# ver11.net
KiCad netlist of a schematic drawn in EAGLE
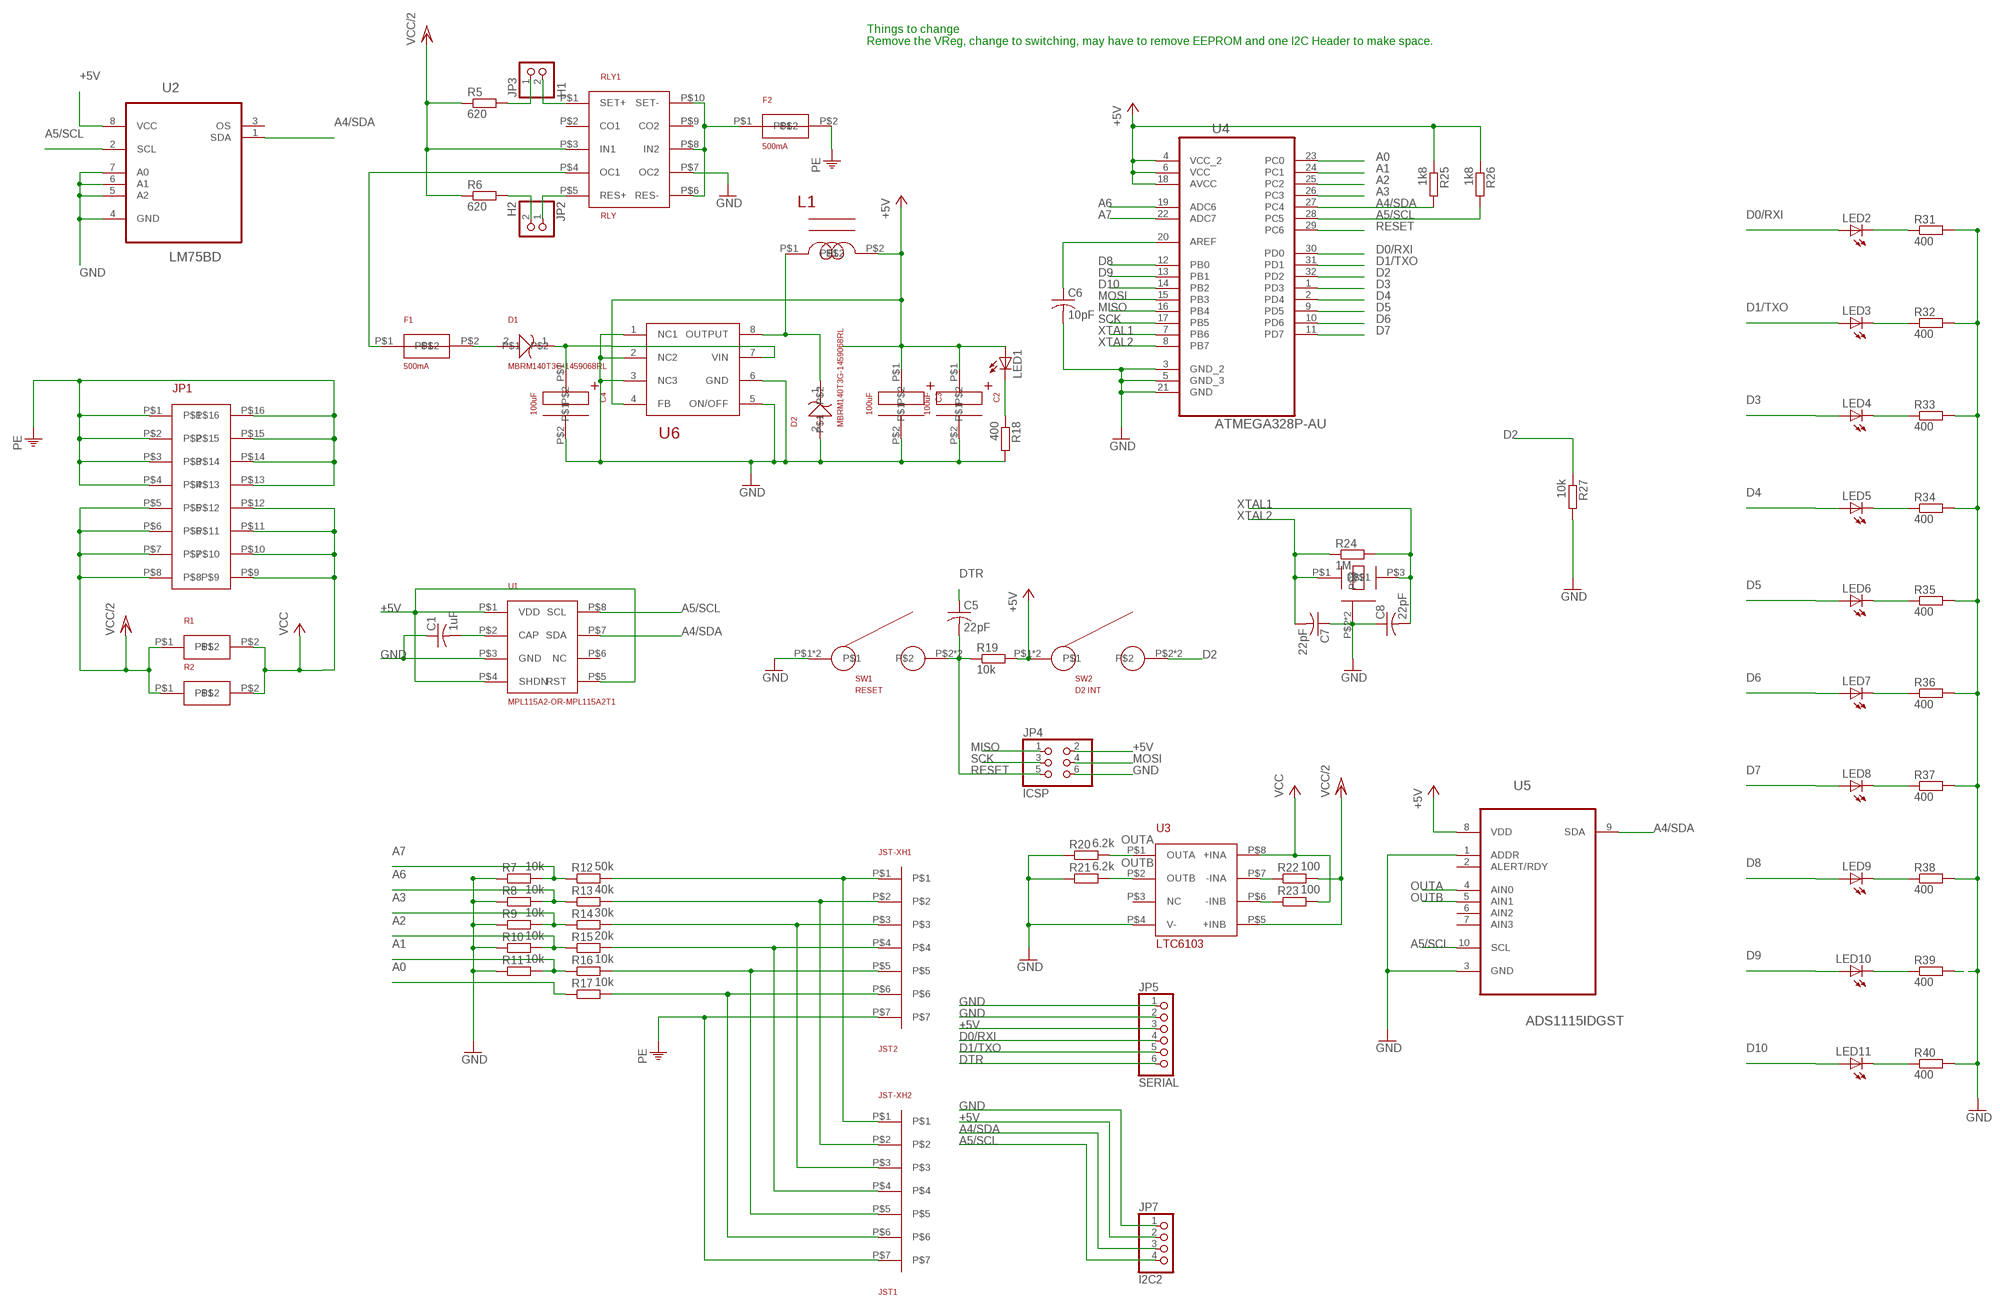
[diagram p0: schematic, sheet 1]

(export (version "E")
  (design (tool "Eeschema 10.0.6"))
  (components
    (comp (ref "C1")
      (value "1uF")
      (footprint "eagle-import:C1206")
      (libsource (lib "eagle-import") (part "C-USC1206"))
    )
    (comp (ref "C2")
      (value "100uF")
      (footprint "eagle-import:EEEFTH101XAP")
      (libsource (lib "eagle-import") (part "EEEFTH101XAP"))
    )
    (comp (ref "C3")
      (value "100uF")
      (footprint "eagle-import:EEEFTH101XAP")
      (libsource (lib "eagle-import") (part "EEEFTH101XAP"))
    )
    (comp (ref "C4")
      (value "100uF")
      (footprint "eagle-import:EEEFTH101XAP")
      (libsource (lib "eagle-import") (part "EEEFTH101XAP"))
    )
    (comp (ref "C5")
      (value "22pF")
      (footprint "eagle-import:C1206")
      (libsource (lib "eagle-import") (part "C-USC1206"))
    )
    (comp (ref "C6")
      (value "10pF")
      (footprint "eagle-import:C1206")
      (libsource (lib "eagle-import") (part "C-USC1206"))
    )
    (comp (ref "C7")
      (value "22pF")
      (footprint "eagle-import:C1206")
      (libsource (lib "eagle-import") (part "C-USC1206"))
    )
    (comp (ref "C8")
      (value "22pF")
      (footprint "eagle-import:C1206")
      (libsource (lib "eagle-import") (part "C-USC1206"))
    )
    (comp (ref "D1")
      (value "MBRM140T3G-1459068RL")
      (footprint "eagle-import:MBRM140T3G-1459068RL")
      (libsource (lib "eagle-import") (part "MBRM140T3G-1459068RL"))
    )
    (comp (ref "D2")
      (value "MBRM140T3G-1459068RL")
      (footprint "eagle-import:MBRM140T3G-1459068RL")
      (libsource (lib "eagle-import") (part "MBRM140T3G-1459068RL"))
    )
    (comp (ref "F1")
      (value "500mA")
      (footprint "eagle-import:MF-MSMF050-2")
      (libsource (lib "eagle-import") (part "MF-MSMF050-2"))
    )
    (comp (ref "F2")
      (value "500mA")
      (footprint "eagle-import:0154.500DR-FUSE-0453.500")
      (libsource (lib "eagle-import") (part "0154.500DR-FUSE-0453.500"))
    )
    (comp (ref "JP1")
      (value "39-29-1167-MOLEX")
      (footprint "eagle-import:39-29-1167-MOLEX")
      (libsource (lib "eagle-import") (part "39-29-1167-MOLEX"))
    )
    (comp (ref "JP2")
      (value "H2")
      (footprint "eagle-import:1X02")
      (libsource (lib "eagle-import") (part "PINHD-1X2"))
    )
    (comp (ref "JP3")
      (value "H1")
      (footprint "eagle-import:1X02")
      (libsource (lib "eagle-import") (part "PINHD-1X2"))
    )
    (comp (ref "JP4")
      (value "ICSP")
      (footprint "eagle-import:2X03")
      (libsource (lib "eagle-import") (part "PINHD-2X3"))
    )
    (comp (ref "JP5")
      (value "SERIAL")
      (footprint "eagle-import:1X06")
      (libsource (lib "eagle-import") (part "PINHD-1X6"))
    )
    (comp (ref "JP7")
      (value "I2C2")
      (footprint "eagle-import:1X04")
      (libsource (lib "eagle-import") (part "PINHD-1X4"))
    )
    (comp (ref "JST-XH1")
      (value "JST2")
      (footprint "eagle-import:JSTXH-7PIN")
      (libsource (lib "eagle-import") (part "JSTXH-7PIN"))
    )
    (comp (ref "JST-XH2")
      (value "JST1")
      (footprint "eagle-import:JSTXH-7PIN")
      (libsource (lib "eagle-import") (part "JSTXH-7PIN"))
    )
    (comp (ref "L1")
      (value "MCSD75-121KU-120UF-INDUCTOR-660MA-1864147")
      (footprint "eagle-import:MCSD75-121KU-120UF-INDUCTOR-660MA-1864147")
      (libsource (lib "eagle-import") (part "MCSD75-121KU-120UF-INDUCTOR-660MA-1864147"))
    )
    (comp (ref "LED1")
      (value "LED1206")
      (footprint "eagle-import:LED-1206")
      (libsource (lib "eagle-import") (part "LED1206"))
    )
    (comp (ref "LED2")
      (value "LED1206")
      (footprint "eagle-import:LED-1206")
      (libsource (lib "eagle-import") (part "LED1206"))
    )
    (comp (ref "LED3")
      (value "LED1206")
      (footprint "eagle-import:LED-1206")
      (libsource (lib "eagle-import") (part "LED1206"))
    )
    (comp (ref "LED4")
      (value "LED1206")
      (footprint "eagle-import:LED-1206")
      (libsource (lib "eagle-import") (part "LED1206"))
    )
    (comp (ref "LED5")
      (value "LED1206")
      (footprint "eagle-import:LED-1206")
      (libsource (lib "eagle-import") (part "LED1206"))
    )
    (comp (ref "LED6")
      (value "LED1206")
      (footprint "eagle-import:LED-1206")
      (libsource (lib "eagle-import") (part "LED1206"))
    )
    (comp (ref "LED7")
      (value "LED1206")
      (footprint "eagle-import:LED-1206")
      (libsource (lib "eagle-import") (part "LED1206"))
    )
    (comp (ref "LED8")
      (value "LED1206")
      (footprint "eagle-import:LED-1206")
      (libsource (lib "eagle-import") (part "LED1206"))
    )
    (comp (ref "LED9")
      (value "LED1206")
      (footprint "eagle-import:LED-1206")
      (libsource (lib "eagle-import") (part "LED1206"))
    )
    (comp (ref "LED10")
      (value "LED1206")
      (footprint "eagle-import:LED-1206")
      (libsource (lib "eagle-import") (part "LED1206"))
    )
    (comp (ref "LED11")
      (value "LED1206")
      (footprint "eagle-import:LED-1206")
      (libsource (lib "eagle-import") (part "LED1206"))
    )
    (comp (ref "R1")
      (value "OARSXPR002FLF")
      (footprint "eagle-import:OARSXPR002FLF")
      (libsource (lib "eagle-import") (part "OARSXPR002FLF"))
    )
    (comp (ref "R2")
      (value "OARSXPR002FLF")
      (footprint "eagle-import:OARSXPR002FLF")
      (libsource (lib "eagle-import") (part "OARSXPR002FLF"))
    )
    (comp (ref "R5")
      (value "620")
      (footprint "eagle-import:R1206")
      (libsource (lib "eagle-import") (part "R-EU_R1206"))
    )
    (comp (ref "R6")
      (value "620")
      (footprint "eagle-import:R1206")
      (libsource (lib "eagle-import") (part "R-EU_R1206"))
    )
    (comp (ref "R7")
      (value "10k")
      (footprint "eagle-import:R1206")
      (libsource (lib "eagle-import") (part "R-EU_R1206"))
    )
    (comp (ref "R8")
      (value "10k")
      (footprint "eagle-import:R1206")
      (libsource (lib "eagle-import") (part "R-EU_R1206"))
    )
    (comp (ref "R9")
      (value "10k")
      (footprint "eagle-import:R1206")
      (libsource (lib "eagle-import") (part "R-EU_R1206"))
    )
    (comp (ref "R10")
      (value "10k")
      (footprint "eagle-import:R1206")
      (libsource (lib "eagle-import") (part "R-EU_R1206"))
    )
    (comp (ref "R11")
      (value "10k")
      (footprint "eagle-import:R1206")
      (libsource (lib "eagle-import") (part "R-EU_R1206"))
    )
    (comp (ref "R12")
      (value "50k")
      (footprint "eagle-import:R1206")
      (libsource (lib "eagle-import") (part "R-EU_R1206"))
    )
    (comp (ref "R13")
      (value "40k")
      (footprint "eagle-import:R1206")
      (libsource (lib "eagle-import") (part "R-EU_R1206"))
    )
    (comp (ref "R14")
      (value "30k")
      (footprint "eagle-import:R1206")
      (libsource (lib "eagle-import") (part "R-EU_R1206"))
    )
    (comp (ref "R15")
      (value "20k")
      (footprint "eagle-import:R1206")
      (libsource (lib "eagle-import") (part "R-EU_R1206"))
    )
    (comp (ref "R16")
      (value "10k")
      (footprint "eagle-import:R1206")
      (libsource (lib "eagle-import") (part "R-EU_R1206"))
    )
    (comp (ref "R17")
      (value "10k")
      (footprint "eagle-import:R1206")
      (libsource (lib "eagle-import") (part "R-EU_R1206"))
    )
    (comp (ref "R18")
      (value "400")
      (footprint "eagle-import:R1206")
      (libsource (lib "eagle-import") (part "R-EU_R1206"))
    )
    (comp (ref "R19")
      (value "10k")
      (footprint "eagle-import:R1206")
      (libsource (lib "eagle-import") (part "R-EU_R1206"))
    )
    (comp (ref "R20")
      (value "6.2k")
      (footprint "eagle-import:R1206")
      (libsource (lib "eagle-import") (part "R-EU_R1206"))
    )
    (comp (ref "R21")
      (value "6.2k")
      (footprint "eagle-import:R1206")
      (libsource (lib "eagle-import") (part "R-EU_R1206"))
    )
    (comp (ref "R22")
      (value "100")
      (footprint "eagle-import:R1206")
      (libsource (lib "eagle-import") (part "R-EU_R1206"))
    )
    (comp (ref "R23")
      (value "100")
      (footprint "eagle-import:R1206")
      (libsource (lib "eagle-import") (part "R-EU_R1206"))
    )
    (comp (ref "R24")
      (value "1M")
      (footprint "eagle-import:R1206")
      (libsource (lib "eagle-import") (part "R-EU_R1206"))
    )
    (comp (ref "R25")
      (value "1k8")
      (footprint "eagle-import:R1206")
      (libsource (lib "eagle-import") (part "R-EU_R1206"))
    )
    (comp (ref "R26")
      (value "1k8")
      (footprint "eagle-import:R1206")
      (libsource (lib "eagle-import") (part "R-EU_R1206"))
    )
    (comp (ref "R27")
      (value "10k")
      (footprint "eagle-import:R1206")
      (libsource (lib "eagle-import") (part "R-EU_R1206"))
    )
    (comp (ref "R31")
      (value "400")
      (footprint "eagle-import:R1206")
      (libsource (lib "eagle-import") (part "R-EU_R1206"))
    )
    (comp (ref "R32")
      (value "400")
      (footprint "eagle-import:R1206")
      (libsource (lib "eagle-import") (part "R-EU_R1206"))
    )
    (comp (ref "R33")
      (value "400")
      (footprint "eagle-import:R1206")
      (libsource (lib "eagle-import") (part "R-EU_R1206"))
    )
    (comp (ref "R34")
      (value "400")
      (footprint "eagle-import:R1206")
      (libsource (lib "eagle-import") (part "R-EU_R1206"))
    )
    (comp (ref "R35")
      (value "400")
      (footprint "eagle-import:R1206")
      (libsource (lib "eagle-import") (part "R-EU_R1206"))
    )
    (comp (ref "R36")
      (value "400")
      (footprint "eagle-import:R1206")
      (libsource (lib "eagle-import") (part "R-EU_R1206"))
    )
    (comp (ref "R37")
      (value "400")
      (footprint "eagle-import:R1206")
      (libsource (lib "eagle-import") (part "R-EU_R1206"))
    )
    (comp (ref "R38")
      (value "400")
      (footprint "eagle-import:R1206")
      (libsource (lib "eagle-import") (part "R-EU_R1206"))
    )
    (comp (ref "R39")
      (value "400")
      (footprint "eagle-import:R1206")
      (libsource (lib "eagle-import") (part "R-EU_R1206"))
    )
    (comp (ref "R40")
      (value "400")
      (footprint "eagle-import:R1206")
      (libsource (lib "eagle-import") (part "R-EU_R1206"))
    )
    (comp (ref "RLY1")
      (value "RLY")
      (footprint "eagle-import:3-1393788-3")
      (libsource (lib "eagle-import") (part "3-1393788-3"))
    )
    (comp (ref "SW1")
      (value "RESET")
      (footprint "eagle-import:MC32829")
      (libsource (lib "eagle-import") (part "MC32829"))
    )
    (comp (ref "SW2")
      (value "D2 INT")
      (footprint "eagle-import:MC32829")
      (libsource (lib "eagle-import") (part "MC32829"))
    )
    (comp (ref "U1")
      (value "MPL115A2-OR-MPL115A2T1")
      (footprint "eagle-import:MPL115A2-OR-MPL115A2T1")
      (libsource (lib "eagle-import") (part "MPL115A2-OR-MPL115A2T1"))
    )
    (comp (ref "U2")
      (value "LM75BD")
      (footprint "eagle-import:SOIC127P600X175-8N")
      (libsource (lib "eagle-import") (part "LM75BD"))
    )
    (comp (ref "U3")
      (value "LTC6103")
      (footprint "eagle-import:LTC6103CMS8#PBF")
      (libsource (lib "eagle-import") (part "LTC6103CMS8#PBF"))
    )
    (comp (ref "U4")
      (value "ATMEGA328P-AU")
      (footprint "eagle-import:QFP80P900X900X120-32N")
      (libsource (lib "eagle-import") (part "ATMEGA328P-AU"))
    )
    (comp (ref "U5")
      (value "ADS1115IDGST")
      (footprint "eagle-import:SOP50P490X110-10N")
      (libsource (lib "eagle-import") (part "ADS1115IDGST"))
    )
    (comp (ref "U6")
      (value "VOLTREG-LM2594MX-5.0/NOPB-1496090")
      (footprint "eagle-import:SO08")
      (libsource (lib "eagle-import") (part "VOLTREG-LM2594MX-5.0/NOPB-1496090"))
    )
    (comp (ref "XT1")
      (value "ABMM2-16.000MHZ-E2-T")
      (footprint "eagle-import:ABMM2-16.000MHZ-E2-T")
      (libsource (lib "eagle-import") (part "ABMM2-16.000MHZ-E2-T"))
    )
  )
  (nets
    (net (code "1") (name "+5V") (class "Default")
      (node (ref "C2") (pin "P$1") (pinfunction "P$1_P$1") (pintype "bidirectional"))
      (node (ref "C3") (pin "P$1") (pinfunction "P$1_P$1") (pintype "bidirectional"))
      (node (ref "JP4") (pin "2") (pinfunction "2_2") (pintype "passive"))
      (node (ref "JP5") (pin "3") (pinfunction "3_3") (pintype "passive"))
      (node (ref "JP7") (pin "2") (pinfunction "2_2") (pintype "passive"))
      (node (ref "L1") (pin "P$2") (pinfunction "P$2_P$2") (pintype "bidirectional"))
      (node (ref "LED1") (pin "A") (pinfunction "A_A") (pintype "passive"))
      (node (ref "R19") (pin "2") (pinfunction "2_2") (pintype "passive"))
      (node (ref "R25") (pin "1") (pinfunction "1_1") (pintype "passive"))
      (node (ref "R26") (pin "1") (pinfunction "1_1") (pintype "passive"))
      (node (ref "SW2") (pin "P$1") (pinfunction "P$1_P$1") (pintype "bidirectional"))
      (node (ref "SW2") (pin "P$4") (pinfunction "P$1_P$4") (pintype "bidirectional"))
      (node (ref "U1") (pin "P$1") (pinfunction "VDD_P$1") (pintype "bidirectional"))
      (node (ref "U1") (pin "P$4") (pinfunction "SHDN_P$4") (pintype "bidirectional"))
      (node (ref "U1") (pin "P$5") (pinfunction "RST_P$5") (pintype "bidirectional"))
      (node (ref "U2") (pin "8") (pinfunction "VCC_8") (pintype "power_in"))
      (node (ref "U4") (pin "18") (pinfunction "AVCC_18") (pintype "power_in"))
      (node (ref "U4") (pin "4") (pinfunction "VCC_2_4") (pintype "power_in"))
      (node (ref "U4") (pin "6") (pinfunction "VCC_6") (pintype "power_in"))
      (node (ref "U5") (pin "8") (pinfunction "VDD_8") (pintype "power_in"))
      (node (ref "U6") (pin "4") (pinfunction "FB_4") (pintype "bidirectional"))
    )
    (net (code "2") (name "/A0") (class "Default")
      (node (ref "R17") (pin "1") (pinfunction "1_1") (pintype "passive"))
      (node (ref "U4") (pin "23") (pinfunction "PC0_23") (pintype "bidirectional"))
    )
    (net (code "3") (name "/A1") (class "Default")
      (node (ref "R11") (pin "2") (pinfunction "2_2") (pintype "passive"))
      (node (ref "R16") (pin "1") (pinfunction "1_1") (pintype "passive"))
      (node (ref "U4") (pin "24") (pinfunction "PC1_24") (pintype "bidirectional"))
    )
    (net (code "4") (name "/A2") (class "Default")
      (node (ref "R10") (pin "2") (pinfunction "2_2") (pintype "passive"))
      (node (ref "R15") (pin "1") (pinfunction "1_1") (pintype "passive"))
      (node (ref "U4") (pin "25") (pinfunction "PC2_25") (pintype "bidirectional"))
    )
    (net (code "5") (name "/A3") (class "Default")
      (node (ref "R14") (pin "1") (pinfunction "1_1") (pintype "passive"))
      (node (ref "R9") (pin "2") (pinfunction "2_2") (pintype "passive"))
      (node (ref "U4") (pin "26") (pinfunction "PC3_26") (pintype "bidirectional"))
    )
    (net (code "6") (name "/A4{slash}SDA") (class "Default")
      (node (ref "JP7") (pin "3") (pinfunction "3_3") (pintype "passive"))
      (node (ref "R25") (pin "2") (pinfunction "2_2") (pintype "passive"))
      (node (ref "U1") (pin "P$7") (pinfunction "SDA_P$7") (pintype "bidirectional"))
      (node (ref "U2") (pin "1") (pinfunction "SDA_1") (pintype "bidirectional"))
      (node (ref "U4") (pin "27") (pinfunction "PC4_27") (pintype "bidirectional"))
      (node (ref "U5") (pin "9") (pinfunction "SDA_9") (pintype "bidirectional"))
    )
    (net (code "7") (name "/A5{slash}SCL") (class "Default")
      (node (ref "JP7") (pin "4") (pinfunction "4_4") (pintype "passive"))
      (node (ref "R26") (pin "2") (pinfunction "2_2") (pintype "passive"))
      (node (ref "U1") (pin "P$8") (pinfunction "SCL_P$8") (pintype "bidirectional"))
      (node (ref "U2") (pin "2") (pinfunction "SCL_2") (pintype "input"))
      (node (ref "U4") (pin "28") (pinfunction "PC5_28") (pintype "bidirectional"))
      (node (ref "U5") (pin "10") (pinfunction "SCL_10") (pintype "input"))
    )
    (net (code "8") (name "/A6") (class "Default")
      (node (ref "R13") (pin "1") (pinfunction "1_1") (pintype "passive"))
      (node (ref "R8") (pin "2") (pinfunction "2_2") (pintype "passive"))
      (node (ref "U4") (pin "19") (pinfunction "ADC6_19") (pintype "input"))
    )
    (net (code "9") (name "/A7") (class "Default")
      (node (ref "R12") (pin "1") (pinfunction "1_1") (pintype "passive"))
      (node (ref "R7") (pin "2") (pinfunction "2_2") (pintype "passive"))
      (node (ref "U4") (pin "22") (pinfunction "ADC7_22") (pintype "input"))
    )
    (net (code "10") (name "/D0{slash}RXI") (class "Default")
      (node (ref "JP5") (pin "4") (pinfunction "4_4") (pintype "passive"))
      (node (ref "LED2") (pin "A") (pinfunction "A_A") (pintype "passive"))
      (node (ref "U4") (pin "30") (pinfunction "PD0_30") (pintype "bidirectional"))
    )
    (net (code "11") (name "/D1{slash}TXO") (class "Default")
      (node (ref "JP5") (pin "5") (pinfunction "5_5") (pintype "passive"))
      (node (ref "LED3") (pin "A") (pinfunction "A_A") (pintype "passive"))
      (node (ref "U4") (pin "31") (pinfunction "PD1_31") (pintype "bidirectional"))
    )
    (net (code "12") (name "/D2") (class "Default")
      (node (ref "R27") (pin "1") (pinfunction "1_1") (pintype "passive"))
      (node (ref "SW2") (pin "P$2") (pinfunction "P$2_P$2") (pintype "bidirectional"))
      (node (ref "SW2") (pin "P$3") (pinfunction "P$2_P$3") (pintype "bidirectional"))
      (node (ref "U4") (pin "32") (pinfunction "PD2_32") (pintype "bidirectional"))
    )
    (net (code "13") (name "/D3") (class "Default")
      (node (ref "LED4") (pin "A") (pinfunction "A_A") (pintype "passive"))
      (node (ref "U4") (pin "1") (pinfunction "PD3_1") (pintype "bidirectional"))
    )
    (net (code "14") (name "/D4") (class "Default")
      (node (ref "LED5") (pin "A") (pinfunction "A_A") (pintype "passive"))
      (node (ref "U4") (pin "2") (pinfunction "PD4_2") (pintype "bidirectional"))
    )
    (net (code "15") (name "/D5") (class "Default")
      (node (ref "LED6") (pin "A") (pinfunction "A_A") (pintype "passive"))
      (node (ref "U4") (pin "9") (pinfunction "PD5_9") (pintype "bidirectional"))
    )
    (net (code "16") (name "/D6") (class "Default")
      (node (ref "LED7") (pin "A") (pinfunction "A_A") (pintype "passive"))
      (node (ref "U4") (pin "10") (pinfunction "PD6_10") (pintype "bidirectional"))
    )
    (net (code "17") (name "/D7") (class "Default")
      (node (ref "LED8") (pin "A") (pinfunction "A_A") (pintype "passive"))
      (node (ref "U4") (pin "11") (pinfunction "PD7_11") (pintype "bidirectional"))
    )
    (net (code "18") (name "/D8") (class "Default")
      (node (ref "LED9") (pin "A") (pinfunction "A_A") (pintype "passive"))
      (node (ref "U4") (pin "12") (pinfunction "PB0_12") (pintype "bidirectional"))
    )
    (net (code "19") (name "/D9") (class "Default")
      (node (ref "LED10") (pin "A") (pinfunction "A_A") (pintype "passive"))
      (node (ref "U4") (pin "13") (pinfunction "PB1_13") (pintype "bidirectional"))
    )
    (net (code "20") (name "/D10") (class "Default")
      (node (ref "LED11") (pin "A") (pinfunction "A_A") (pintype "passive"))
      (node (ref "U4") (pin "14") (pinfunction "PB2_14") (pintype "bidirectional"))
    )
    (net (code "21") (name "/DTR") (class "Default")
      (node (ref "C5") (pin "1") (pinfunction "1_1") (pintype "passive"))
      (node (ref "JP5") (pin "6") (pinfunction "6_6") (pintype "passive"))
    )
    (net (code "22") (name "/MISO") (class "Default")
      (node (ref "JP4") (pin "1") (pinfunction "1_1") (pintype "passive"))
      (node (ref "U4") (pin "16") (pinfunction "PB4_16") (pintype "bidirectional"))
    )
    (net (code "23") (name "/MOSI") (class "Default")
      (node (ref "JP4") (pin "4") (pinfunction "4_4") (pintype "passive"))
      (node (ref "U4") (pin "15") (pinfunction "PB3_15") (pintype "bidirectional"))
    )
    (net (code "24") (name "/OUTA") (class "Default")
      (node (ref "R20") (pin "2") (pinfunction "2_2") (pintype "passive"))
      (node (ref "U3") (pin "P$1") (pinfunction "OUTA_P$1") (pintype "bidirectional"))
      (node (ref "U5") (pin "4") (pinfunction "AIN0_4") (pintype "input"))
    )
    (net (code "25") (name "/OUTB") (class "Default")
      (node (ref "R21") (pin "2") (pinfunction "2_2") (pintype "passive"))
      (node (ref "U3") (pin "P$2") (pinfunction "OUTB_P$2") (pintype "bidirectional"))
      (node (ref "U5") (pin "5") (pinfunction "AIN1_5") (pintype "input"))
    )
    (net (code "26") (name "/RESET") (class "Default")
      (node (ref "C5") (pin "2") (pinfunction "2_2") (pintype "passive"))
      (node (ref "JP4") (pin "5") (pinfunction "5_5") (pintype "passive"))
      (node (ref "R19") (pin "1") (pinfunction "1_1") (pintype "passive"))
      (node (ref "SW1") (pin "P$2") (pinfunction "P$2_P$2") (pintype "bidirectional"))
      (node (ref "SW1") (pin "P$3") (pinfunction "P$2_P$3") (pintype "bidirectional"))
      (node (ref "U4") (pin "29") (pinfunction "PC6_29") (pintype "bidirectional"))
    )
    (net (code "27") (name "/SCK") (class "Default")
      (node (ref "JP4") (pin "3") (pinfunction "3_3") (pintype "passive"))
      (node (ref "U4") (pin "17") (pinfunction "PB5_17") (pintype "bidirectional"))
    )
    (net (code "28") (name "/XTAL1") (class "Default")
      (node (ref "C8") (pin "2") (pinfunction "2_2") (pintype "passive"))
      (node (ref "R24") (pin "2") (pinfunction "2_2") (pintype "passive"))
      (node (ref "U4") (pin "7") (pinfunction "PB6_7") (pintype "bidirectional"))
      (node (ref "XT1") (pin "P$3") (pinfunction "P$2_P$3") (pintype "bidirectional"))
    )
    (net (code "29") (name "/XTAL2") (class "Default")
      (node (ref "C7") (pin "2") (pinfunction "2_2") (pintype "passive"))
      (node (ref "R24") (pin "1") (pinfunction "1_1") (pintype "passive"))
      (node (ref "U4") (pin "8") (pinfunction "PB7_8") (pintype "bidirectional"))
      (node (ref "XT1") (pin "P$1") (pinfunction "P$1_P$1") (pintype "bidirectional"))
    )
    (net (code "30") (name "GND") (class "Default")
      (node (ref "C1") (pin "1") (pinfunction "1_1") (pintype "passive"))
      (node (ref "C2") (pin "P$2") (pinfunction "P$2_P$2") (pintype "bidirectional"))
      (node (ref "C3") (pin "P$2") (pinfunction "P$2_P$2") (pintype "bidirectional"))
      (node (ref "C4") (pin "P$2") (pinfunction "P$2_P$2") (pintype "bidirectional"))
      (node (ref "C6") (pin "2") (pinfunction "2_2") (pintype "passive"))
      (node (ref "C7") (pin "1") (pinfunction "1_1") (pintype "passive"))
      (node (ref "C8") (pin "1") (pinfunction "1_1") (pintype "passive"))
      (node (ref "D2") (pin "2") (pinfunction "P$2_2") (pintype "bidirectional"))
      (node (ref "JP4") (pin "6") (pinfunction "6_6") (pintype "passive"))
      (node (ref "JP5") (pin "1") (pinfunction "1_1") (pintype "passive"))
      (node (ref "JP5") (pin "2") (pinfunction "2_2") (pintype "passive"))
      (node (ref "JP7") (pin "1") (pinfunction "1_1") (pintype "passive"))
      (node (ref "R10") (pin "1") (pinfunction "1_1") (pintype "passive"))
      (node (ref "R11") (pin "1") (pinfunction "1_1") (pintype "passive"))
      (node (ref "R18") (pin "2") (pinfunction "2_2") (pintype "passive"))
      (node (ref "R20") (pin "1") (pinfunction "1_1") (pintype "passive"))
      (node (ref "R21") (pin "1") (pinfunction "1_1") (pintype "passive"))
      (node (ref "R27") (pin "2") (pinfunction "2_2") (pintype "passive"))
      (node (ref "R31") (pin "2") (pinfunction "2_2") (pintype "passive"))
      (node (ref "R32") (pin "2") (pinfunction "2_2") (pintype "passive"))
      (node (ref "R33") (pin "2") (pinfunction "2_2") (pintype "passive"))
      (node (ref "R34") (pin "2") (pinfunction "2_2") (pintype "passive"))
      (node (ref "R35") (pin "2") (pinfunction "2_2") (pintype "passive"))
      (node (ref "R36") (pin "2") (pinfunction "2_2") (pintype "passive"))
      (node (ref "R37") (pin "2") (pinfunction "2_2") (pintype "passive"))
      (node (ref "R38") (pin "2") (pinfunction "2_2") (pintype "passive"))
      (node (ref "R39") (pin "2") (pinfunction "2_2") (pintype "passive"))
      (node (ref "R40") (pin "2") (pinfunction "2_2") (pintype "passive"))
      (node (ref "R7") (pin "1") (pinfunction "1_1") (pintype "passive"))
      (node (ref "R8") (pin "1") (pinfunction "1_1") (pintype "passive"))
      (node (ref "R9") (pin "1") (pinfunction "1_1") (pintype "passive"))
      (node (ref "RLY1") (pin "P$7") (pinfunction "OC2_P$7") (pintype "bidirectional"))
      (node (ref "SW1") (pin "P$1") (pinfunction "P$1_P$1") (pintype "bidirectional"))
      (node (ref "SW1") (pin "P$4") (pinfunction "P$1_P$4") (pintype "bidirectional"))
      (node (ref "U1") (pin "P$3") (pinfunction "GND_P$3") (pintype "bidirectional"))
      (node (ref "U2") (pin "4") (pinfunction "GND_4") (pintype "passive"))
      (node (ref "U2") (pin "5") (pinfunction "A2_5") (pintype "input"))
      (node (ref "U2") (pin "6") (pinfunction "A1_6") (pintype "input"))
      (node (ref "U2") (pin "7") (pinfunction "A0_7") (pintype "input"))
      (node (ref "U3") (pin "P$4") (pinfunction "V-_P$4") (pintype "bidirectional"))
      (node (ref "U4") (pin "21") (pinfunction "GND_21") (pintype "passive"))
      (node (ref "U4") (pin "3") (pinfunction "GND_2_3") (pintype "passive"))
      (node (ref "U4") (pin "5") (pinfunction "GND_3_5") (pintype "passive"))
      (node (ref "U5") (pin "1") (pinfunction "ADDR_1") (pintype "input"))
      (node (ref "U5") (pin "3") (pinfunction "GND_3") (pintype "passive"))
      (node (ref "U6") (pin "1") (pinfunction "NC1_1") (pintype "bidirectional"))
      (node (ref "U6") (pin "2") (pinfunction "NC2_2") (pintype "bidirectional"))
      (node (ref "U6") (pin "3") (pinfunction "NC3_3") (pintype "bidirectional"))
      (node (ref "U6") (pin "5") (pinfunction "ON/OFF_5") (pintype "bidirectional"))
      (node (ref "U6") (pin "6") (pinfunction "GND_6") (pintype "bidirectional"))
      (node (ref "XT1") (pin "P$2") (pinfunction "P$3_P$2") (pintype "bidirectional"))
      (node (ref "XT1") (pin "P$4") (pinfunction "P$3_P$4") (pintype "bidirectional"))
    )
    (net (code "31") (name "Net-(D1-P$1)") (class "Default")
      (node (ref "C4") (pin "P$1") (pinfunction "P$1_P$1") (pintype "bidirectional"))
      (node (ref "D1") (pin "1") (pinfunction "P$1_1") (pintype "bidirectional"))
      (node (ref "U6") (pin "7") (pinfunction "VIN_7") (pintype "bidirectional"))
    )
    (net (code "32") (name "Net-(D1-P$2)") (class "Default")
      (node (ref "D1") (pin "2") (pinfunction "P$2_2") (pintype "bidirectional"))
      (node (ref "F1") (pin "P$2") (pinfunction "P$2_P$2") (pintype "bidirectional"))
    )
    (net (code "33") (name "Net-(D2-P$1)") (class "Default")
      (node (ref "D2") (pin "1") (pinfunction "P$1_1") (pintype "bidirectional"))
      (node (ref "L1") (pin "P$1") (pinfunction "P$1_P$1") (pintype "bidirectional"))
      (node (ref "U6") (pin "8") (pinfunction "OUTPUT_8") (pintype "bidirectional"))
    )
    (net (code "34") (name "Net-(JP2-Pad2)") (class "Default")
      (node (ref "JP2") (pin "2") (pinfunction "2_2") (pintype "passive"))
      (node (ref "R6") (pin "2") (pinfunction "2_2") (pintype "passive"))
    )
    (net (code "35") (name "Net-(JP3-Pad1)") (class "Default")
      (node (ref "JP3") (pin "1") (pinfunction "1_1") (pintype "passive"))
      (node (ref "R5") (pin "2") (pinfunction "2_2") (pintype "passive"))
    )
    (net (code "36") (name "Net-(JST-XH1-PadP$1)") (class "Default")
      (node (ref "JST-XH1") (pin "P$1") (pinfunction "P$1_P$1") (pintype "bidirectional"))
      (node (ref "JST-XH2") (pin "P$1") (pinfunction "P$1_P$1") (pintype "bidirectional"))
      (node (ref "R12") (pin "2") (pinfunction "2_2") (pintype "passive"))
    )
    (net (code "37") (name "Net-(JST-XH1-PadP$2)") (class "Default")
      (node (ref "JST-XH1") (pin "P$2") (pinfunction "P$2_P$2") (pintype "bidirectional"))
      (node (ref "JST-XH2") (pin "P$2") (pinfunction "P$2_P$2") (pintype "bidirectional"))
      (node (ref "R13") (pin "2") (pinfunction "2_2") (pintype "passive"))
    )
    (net (code "38") (name "Net-(JST-XH1-PadP$3)") (class "Default")
      (node (ref "JST-XH1") (pin "P$3") (pinfunction "P$3_P$3") (pintype "bidirectional"))
      (node (ref "JST-XH2") (pin "P$3") (pinfunction "P$3_P$3") (pintype "bidirectional"))
      (node (ref "R14") (pin "2") (pinfunction "2_2") (pintype "passive"))
    )
    (net (code "39") (name "Net-(JST-XH1-PadP$4)") (class "Default")
      (node (ref "JST-XH1") (pin "P$4") (pinfunction "P$4_P$4") (pintype "bidirectional"))
      (node (ref "JST-XH2") (pin "P$4") (pinfunction "P$4_P$4") (pintype "bidirectional"))
      (node (ref "R15") (pin "2") (pinfunction "2_2") (pintype "passive"))
    )
    (net (code "40") (name "Net-(JST-XH1-PadP$5)") (class "Default")
      (node (ref "JST-XH1") (pin "P$5") (pinfunction "P$5_P$5") (pintype "bidirectional"))
      (node (ref "JST-XH2") (pin "P$5") (pinfunction "P$5_P$5") (pintype "bidirectional"))
      (node (ref "R16") (pin "2") (pinfunction "2_2") (pintype "passive"))
    )
    (net (code "41") (name "Net-(JST-XH1-PadP$6)") (class "Default")
      (node (ref "JST-XH1") (pin "P$6") (pinfunction "P$6_P$6") (pintype "bidirectional"))
      (node (ref "JST-XH2") (pin "P$6") (pinfunction "P$6_P$6") (pintype "bidirectional"))
      (node (ref "R17") (pin "2") (pinfunction "2_2") (pintype "passive"))
    )
    (net (code "42") (name "Net-(LED1-PadC)") (class "Default")
      (node (ref "LED1") (pin "C") (pinfunction "C_C") (pintype "passive"))
      (node (ref "R18") (pin "1") (pinfunction "1_1") (pintype "passive"))
    )
    (net (code "43") (name "Net-(LED2-PadC)") (class "Default")
      (node (ref "LED2") (pin "C") (pinfunction "C_C") (pintype "passive"))
      (node (ref "R31") (pin "1") (pinfunction "1_1") (pintype "passive"))
    )
    (net (code "44") (name "Net-(LED3-PadC)") (class "Default")
      (node (ref "LED3") (pin "C") (pinfunction "C_C") (pintype "passive"))
      (node (ref "R32") (pin "1") (pinfunction "1_1") (pintype "passive"))
    )
    (net (code "45") (name "Net-(LED4-PadC)") (class "Default")
      (node (ref "LED4") (pin "C") (pinfunction "C_C") (pintype "passive"))
      (node (ref "R33") (pin "1") (pinfunction "1_1") (pintype "passive"))
    )
    (net (code "46") (name "Net-(LED5-PadC)") (class "Default")
      (node (ref "LED5") (pin "C") (pinfunction "C_C") (pintype "passive"))
      (node (ref "R34") (pin "1") (pinfunction "1_1") (pintype "passive"))
    )
    (net (code "47") (name "Net-(LED6-PadC)") (class "Default")
      (node (ref "LED6") (pin "C") (pinfunction "C_C") (pintype "passive"))
      (node (ref "R35") (pin "1") (pinfunction "1_1") (pintype "passive"))
    )
    (net (code "48") (name "Net-(LED7-PadC)") (class "Default")
      (node (ref "LED7") (pin "C") (pinfunction "C_C") (pintype "passive"))
      (node (ref "R36") (pin "1") (pinfunction "1_1") (pintype "passive"))
    )
    (net (code "49") (name "Net-(LED8-PadC)") (class "Default")
      (node (ref "LED8") (pin "C") (pinfunction "C_C") (pintype "passive"))
      (node (ref "R37") (pin "1") (pinfunction "1_1") (pintype "passive"))
    )
    (net (code "50") (name "Net-(LED9-PadC)") (class "Default")
      (node (ref "LED9") (pin "C") (pinfunction "C_C") (pintype "passive"))
      (node (ref "R38") (pin "1") (pinfunction "1_1") (pintype "passive"))
    )
    (net (code "51") (name "Net-(LED10-PadC)") (class "Default")
      (node (ref "LED10") (pin "C") (pinfunction "C_C") (pintype "passive"))
      (node (ref "R39") (pin "1") (pinfunction "1_1") (pintype "passive"))
    )
    (net (code "52") (name "Net-(LED11-PadC)") (class "Default")
      (node (ref "LED11") (pin "C") (pinfunction "C_C") (pintype "passive"))
      (node (ref "R40") (pin "1") (pinfunction "1_1") (pintype "passive"))
    )
    (net (code "53") (name "Net-(RLY1-IN2)") (class "Default")
      (node (ref "F2") (pin "P$1") (pinfunction "P$1_P$1") (pintype "bidirectional"))
      (node (ref "RLY1") (pin "P$10") (pinfunction "SET-_P$10") (pintype "bidirectional"))
      (node (ref "RLY1") (pin "P$6") (pinfunction "RES-_P$6") (pintype "bidirectional"))
      (node (ref "RLY1") (pin "P$8") (pinfunction "IN2_P$8") (pintype "bidirectional"))
    )
    (net (code "54") (name "Net-(RLY1-OC1)") (class "Default")
      (node (ref "F1") (pin "P$1") (pinfunction "P$1_P$1") (pintype "bidirectional"))
      (node (ref "RLY1") (pin "P$4") (pinfunction "OC1_P$4") (pintype "bidirectional"))
    )
    (net (code "55") (name "Net-(RLY1-RES+)") (class "Default")
      (node (ref "JP2") (pin "1") (pinfunction "1_1") (pintype "passive"))
      (node (ref "RLY1") (pin "P$5") (pinfunction "RES+_P$5") (pintype "bidirectional"))
    )
    (net (code "56") (name "Net-(RLY1-SET+)") (class "Default")
      (node (ref "JP3") (pin "2") (pinfunction "2_2") (pintype "passive"))
      (node (ref "RLY1") (pin "P$1") (pinfunction "SET+_P$1") (pintype "bidirectional"))
    )
    (net (code "57") (name "Net-(U1-CAP)") (class "Default")
      (node (ref "C1") (pin "2") (pinfunction "2_2") (pintype "passive"))
      (node (ref "U1") (pin "P$2") (pinfunction "CAP_P$2") (pintype "bidirectional"))
    )
    (net (code "58") (name "Net-(U3--INA)") (class "Default")
      (node (ref "R22") (pin "1") (pinfunction "1_1") (pintype "passive"))
      (node (ref "U3") (pin "P$7") (pinfunction "-INA_P$7") (pintype "bidirectional"))
    )
    (net (code "59") (name "Net-(U3--INB)") (class "Default")
      (node (ref "R23") (pin "1") (pinfunction "1_1") (pintype "passive"))
      (node (ref "U3") (pin "P$6") (pinfunction "-INB_P$6") (pintype "bidirectional"))
    )
    (net (code "60") (name "Net-(U4-AREF)") (class "Default")
      (node (ref "C6") (pin "1") (pinfunction "1_1") (pintype "passive"))
      (node (ref "U4") (pin "20") (pinfunction "AREF_20") (pintype "input"))
    )
    (net (code "61") (name "PE") (class "Default")
      (node (ref "F2") (pin "P$2") (pinfunction "P$2_P$2") (pintype "bidirectional"))
      (node (ref "JP1") (pin "P$1") (pinfunction "P$1_P$1") (pintype "bidirectional"))
      (node (ref "JP1") (pin "P$13") (pinfunction "P$13_P$13") (pintype "bidirectional"))
      (node (ref "JP1") (pin "P$14") (pinfunction "P$14_P$14") (pintype "bidirectional"))
      (node (ref "JP1") (pin "P$15") (pinfunction "P$15_P$15") (pintype "bidirectional"))
      (node (ref "JP1") (pin "P$16") (pinfunction "P$16_P$16") (pintype "bidirectional"))
      (node (ref "JP1") (pin "P$2") (pinfunction "P$2_P$2") (pintype "bidirectional"))
      (node (ref "JP1") (pin "P$3") (pinfunction "P$3_P$3") (pintype "bidirectional"))
      (node (ref "JP1") (pin "P$4") (pinfunction "P$4_P$4") (pintype "bidirectional"))
      (node (ref "JST-XH1") (pin "P$7") (pinfunction "P$7_P$7") (pintype "bidirectional"))
      (node (ref "JST-XH2") (pin "P$7") (pinfunction "P$7_P$7") (pintype "bidirectional"))
    )
    (net (code "62") (name "VCC") (class "Default")
      (node (ref "JP1") (pin "P$10") (pinfunction "P$10_P$10") (pintype "bidirectional"))
      (node (ref "JP1") (pin "P$11") (pinfunction "P$11_P$11") (pintype "bidirectional"))
      (node (ref "JP1") (pin "P$12") (pinfunction "P$12_P$12") (pintype "bidirectional"))
      (node (ref "JP1") (pin "P$9") (pinfunction "P$9_P$9") (pintype "bidirectional"))
      (node (ref "R1") (pin "P$2") (pinfunction "P$2_P$2") (pintype "bidirectional"))
      (node (ref "R2") (pin "P$2") (pinfunction "P$2_P$2") (pintype "bidirectional"))
      (node (ref "R23") (pin "2") (pinfunction "2_2") (pintype "passive"))
      (node (ref "U3") (pin "P$8") (pinfunction "+INA_P$8") (pintype "bidirectional"))
    )
    (net (code "63") (name "VCC{slash}2") (class "Default")
      (node (ref "JP1") (pin "P$5") (pinfunction "P$5_P$5") (pintype "bidirectional"))
      (node (ref "JP1") (pin "P$6") (pinfunction "P$6_P$6") (pintype "bidirectional"))
      (node (ref "JP1") (pin "P$7") (pinfunction "P$7_P$7") (pintype "bidirectional"))
      (node (ref "JP1") (pin "P$8") (pinfunction "P$8_P$8") (pintype "bidirectional"))
      (node (ref "R1") (pin "P$1") (pinfunction "P$1_P$1") (pintype "bidirectional"))
      (node (ref "R2") (pin "P$1") (pinfunction "P$1_P$1") (pintype "bidirectional"))
      (node (ref "R22") (pin "2") (pinfunction "2_2") (pintype "passive"))
      (node (ref "R5") (pin "1") (pinfunction "1_1") (pintype "passive"))
      (node (ref "R6") (pin "1") (pinfunction "1_1") (pintype "passive"))
      (node (ref "RLY1") (pin "P$3") (pinfunction "IN1_P$3") (pintype "bidirectional"))
      (node (ref "U3") (pin "P$5") (pinfunction "+INB_P$5") (pintype "bidirectional"))
    )
    (net (code "64") (name "unconnected-(RLY1-CO1-PadP$2)") (class "Default")
      (node (ref "RLY1") (pin "P$2") (pinfunction "CO1_P$2") (pintype "bidirectional"))
    )
    (net (code "65") (name "unconnected-(RLY1-CO2-PadP$9)") (class "Default")
      (node (ref "RLY1") (pin "P$9") (pinfunction "CO2_P$9") (pintype "bidirectional"))
    )
    (net (code "66") (name "unconnected-(U1-NC-PadP$6)") (class "Default")
      (node (ref "U1") (pin "P$6") (pinfunction "NC_P$6") (pintype "bidirectional"))
    )
    (net (code "67") (name "unconnected-(U2-OS-Pad3)") (class "Default")
      (node (ref "U2") (pin "3") (pinfunction "OS_3") (pintype "output"))
    )
    (net (code "68") (name "unconnected-(U3-NC-PadP$3)") (class "Default")
      (node (ref "U3") (pin "P$3") (pinfunction "NC_P$3") (pintype "bidirectional"))
    )
    (net (code "69") (name "unconnected-(U5-AIN2-Pad6)") (class "Default")
      (node (ref "U5") (pin "6") (pinfunction "AIN2_6") (pintype "input"))
    )
    (net (code "70") (name "unconnected-(U5-AIN3-Pad7)") (class "Default")
      (node (ref "U5") (pin "7") (pinfunction "AIN3_7") (pintype "input"))
    )
    (net (code "71") (name "unconnected-(U5-ALERT{slash}RDY-Pad2)") (class "Default")
      (node (ref "U5") (pin "2") (pinfunction "ALERT/RDY_2") (pintype "input"))
    )
  )
)
